# Passive_Balancing.net
KiCad netlist of a schematic drawn in Altium Designer
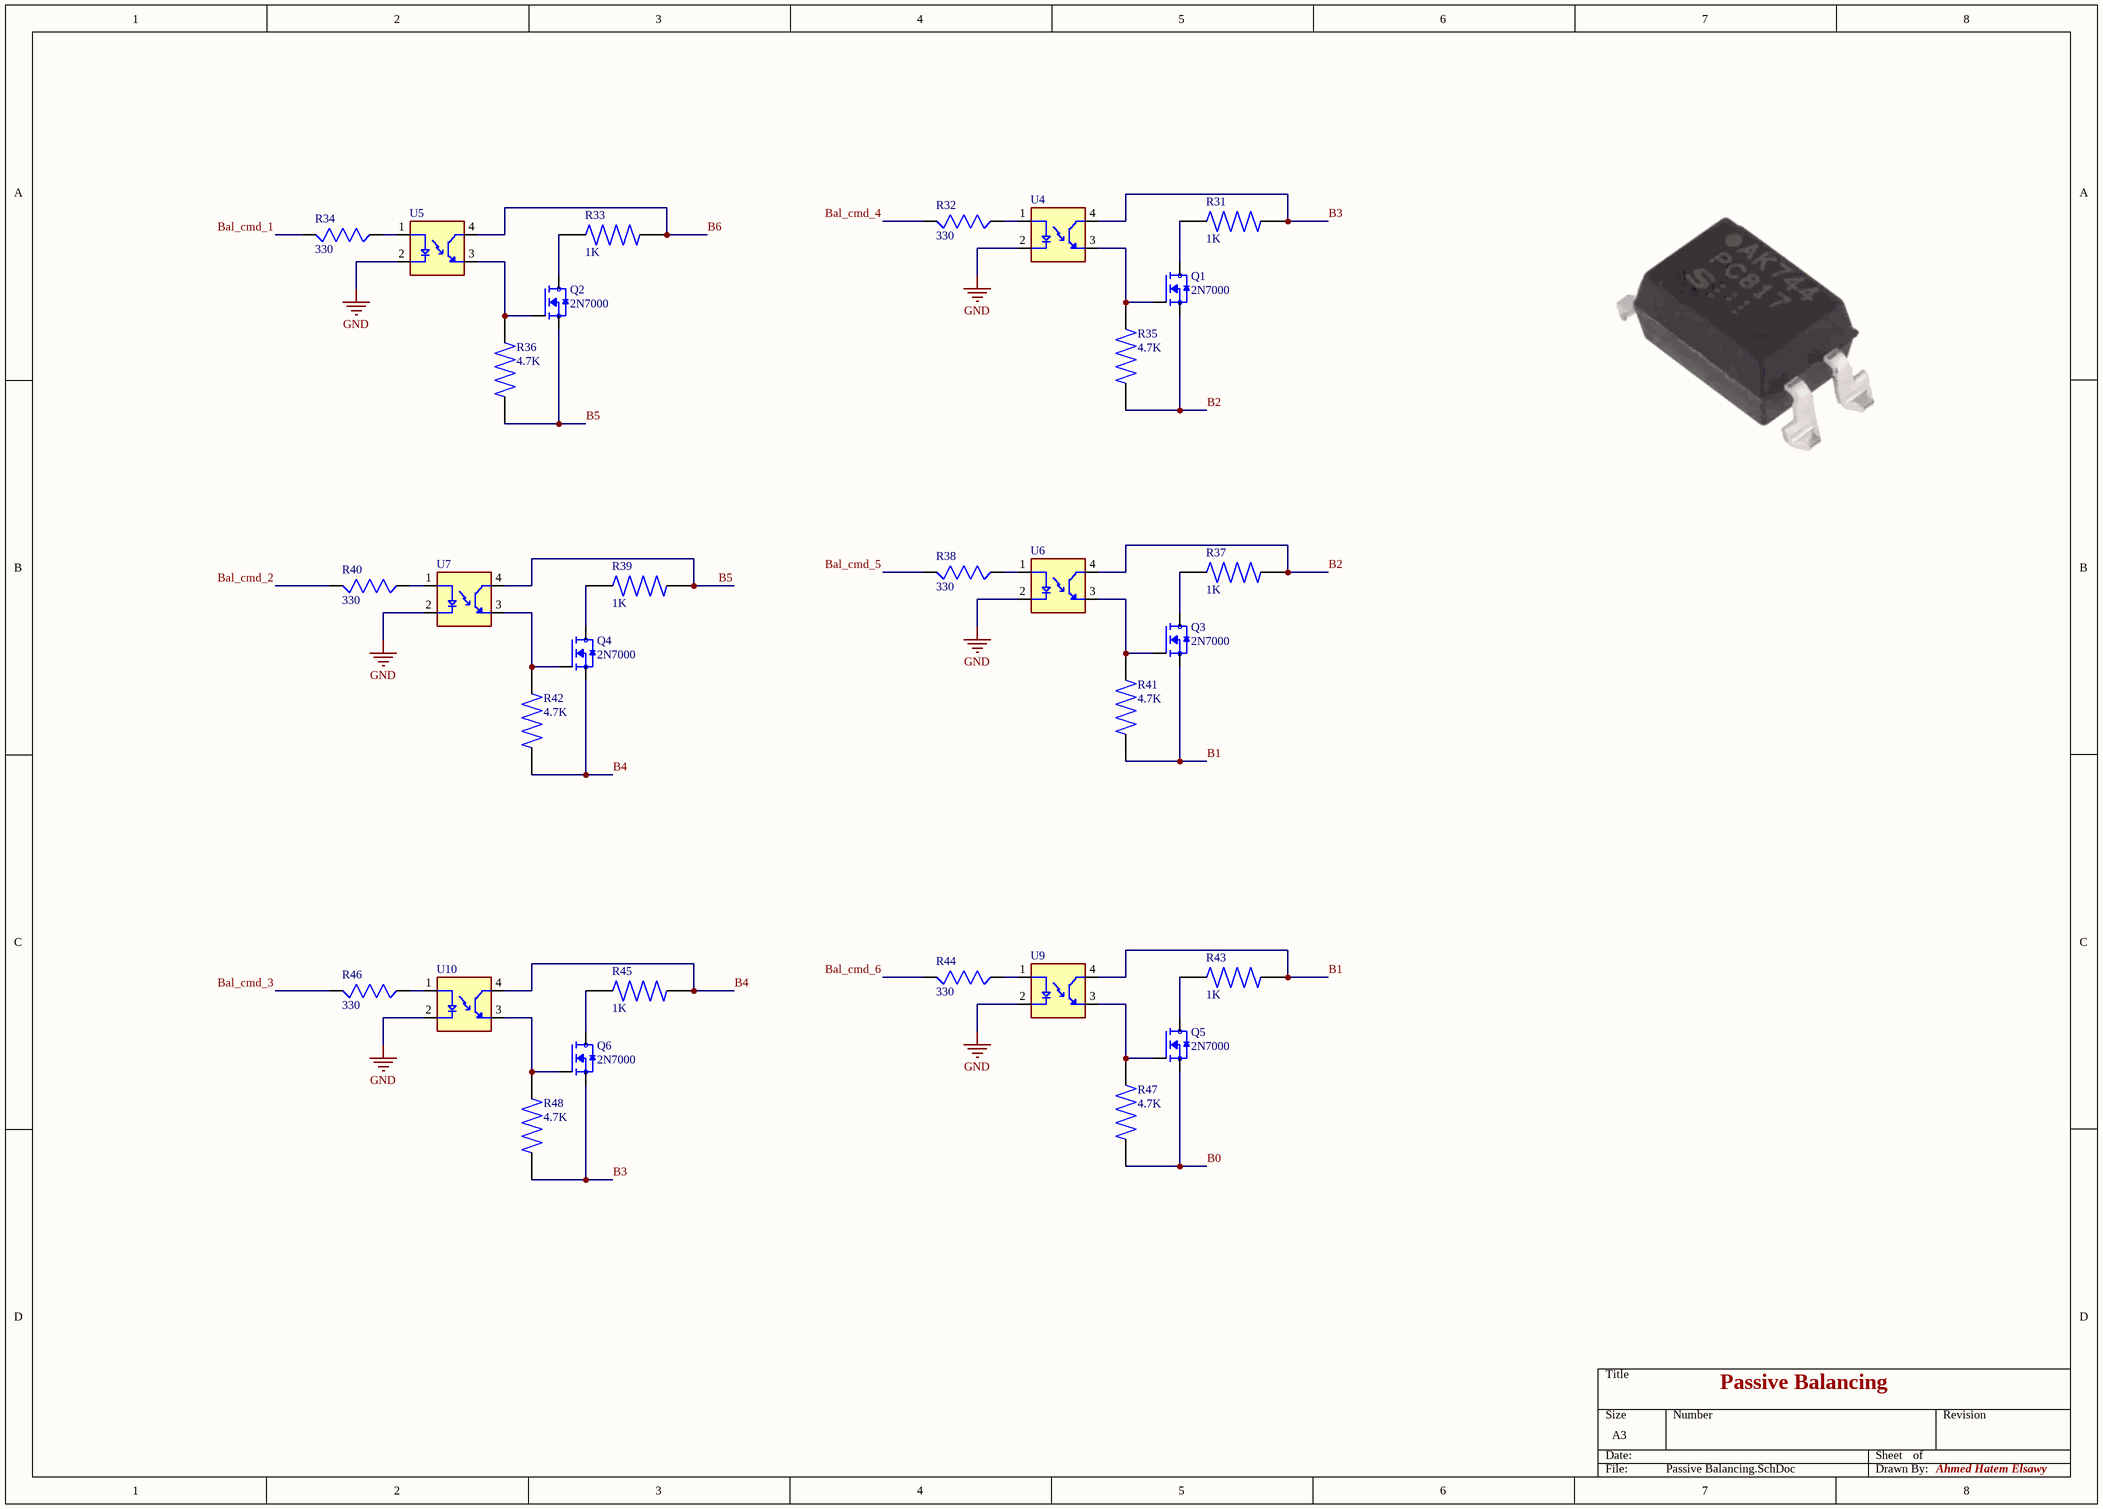
[diagram p0: Passive Balancing.SchDoc]

(export (version "E")
  (design (tool "Eeschema 10.0.6"))
  (components
    (comp (ref "Q1")
      (value "2N7000")
      (footprint "TO92254P458H750-3")
      (description "N-Channel 60 V 350mA (Tc) 1W (Tc) Through Hole TO-92-3")
      (fields (field (name "MF") "STMicroelectronics"))
      (libsource (lib "2N7000") (part "2N7000"))
    )
    (comp (ref "Q2")
      (value "2N7000")
      (footprint "TO92254P458H750-3")
      (description "N-Channel 60 V 350mA (Tc) 1W (Tc) Through Hole TO-92-3")
      (fields (field (name "MF") "STMicroelectronics"))
      (libsource (lib "2N7000") (part "2N7000"))
    )
    (comp (ref "Q3")
      (value "2N7000")
      (footprint "TO92254P458H750-3")
      (description "N-Channel 60 V 350mA (Tc) 1W (Tc) Through Hole TO-92-3")
      (fields (field (name "MF") "STMicroelectronics"))
      (libsource (lib "2N7000") (part "2N7000"))
    )
    (comp (ref "Q4")
      (value "2N7000")
      (footprint "TO92254P458H750-3")
      (description "N-Channel 60 V 350mA (Tc) 1W (Tc) Through Hole TO-92-3")
      (fields (field (name "MF") "STMicroelectronics"))
      (libsource (lib "2N7000") (part "2N7000"))
    )
    (comp (ref "Q5")
      (value "2N7000")
      (footprint "TO92254P458H750-3")
      (description "N-Channel 60 V 350mA (Tc) 1W (Tc) Through Hole TO-92-3")
      (fields (field (name "MF") "STMicroelectronics"))
      (libsource (lib "2N7000") (part "2N7000"))
    )
    (comp (ref "Q6")
      (value "2N7000")
      (footprint "TO92254P458H750-3")
      (description "N-Channel 60 V 350mA (Tc) 1W (Tc) Through Hole TO-92-3")
      (fields (field (name "MF") "STMicroelectronics"))
      (libsource (lib "2N7000") (part "2N7000"))
    )
    (comp (ref "R31")
      (value "1K")
      (footprint "RESC1608X55N")
      (description "DirenÃ§, AS 0603 1k %1 100mW TC100 ¦ Bourns CR0603AFX-1001EAS")
      (fields (field (name "MF") "Bourns") (field (name "MP") "CR0603AFX-1001EAS"))
      (libsource (lib "CR0603AFX-1001EAS") (part "CR0603AFX-1001EAS"))
    )
    (comp (ref "R32")
      (value "330")
      (footprint "RESC3216X65")
      (description "Res Thick Film 1206 330 Ohm 5% 0.25W(1/4W) Â±100ppm/Â°C Epoxy Pad SMD T/R")
      (fields (field (name "MF") "Yageo Corporation") (field (name "MP") "RC1206JR13330RL"))
      (libsource (lib "RC1206JR-13330RL") (part "RC1206JR-13330RL"))
    )
    (comp (ref "R33")
      (value "1K")
      (footprint "RESC1608X55N")
      (description "DirenÃ§, AS 0603 1k %1 100mW TC100 ¦ Bourns CR0603AFX-1001EAS")
      (fields (field (name "MF") "Bourns") (field (name "MP") "CR0603AFX-1001EAS"))
      (libsource (lib "CR0603AFX-1001EAS") (part "CR0603AFX-1001EAS"))
    )
    (comp (ref "R34")
      (value "330")
      (footprint "RESC3216X65")
      (description "Res Thick Film 1206 330 Ohm 5% 0.25W(1/4W) Â±100ppm/Â°C Epoxy Pad SMD T/R")
      (fields (field (name "MF") "Yageo Corporation") (field (name "MP") "RC1206JR13330RL"))
      (libsource (lib "RC1206JR-13330RL") (part "RC1206JR-13330RL"))
    )
    (comp (ref "R35")
      (value "4.7K")
      (footprint "RES_ERJS06J472V")
      (fields (field (name "MP") "ERJS06J472V"))
      (libsource (lib "ERJS06J472V") (part "ERJS06J472V"))
    )
    (comp (ref "R36")
      (value "4.7K")
      (footprint "RES_ERJS06J472V")
      (fields (field (name "MP") "ERJS06J472V"))
      (libsource (lib "ERJS06J472V") (part "ERJS06J472V"))
    )
    (comp (ref "R37")
      (value "1K")
      (footprint "RESC1608X55N")
      (description "DirenÃ§, AS 0603 1k %1 100mW TC100 ¦ Bourns CR0603AFX-1001EAS")
      (fields (field (name "MF") "Bourns") (field (name "MP") "CR0603AFX-1001EAS"))
      (libsource (lib "CR0603AFX-1001EAS") (part "CR0603AFX-1001EAS"))
    )
    (comp (ref "R38")
      (value "330")
      (footprint "RESC3216X65")
      (description "Res Thick Film 1206 330 Ohm 5% 0.25W(1/4W) Â±100ppm/Â°C Epoxy Pad SMD T/R")
      (fields (field (name "MF") "Yageo Corporation") (field (name "MP") "RC1206JR13330RL"))
      (libsource (lib "RC1206JR-13330RL") (part "RC1206JR-13330RL"))
    )
    (comp (ref "R39")
      (value "1K")
      (footprint "RESC1608X55N")
      (description "DirenÃ§, AS 0603 1k %1 100mW TC100 ¦ Bourns CR0603AFX-1001EAS")
      (fields (field (name "MF") "Bourns") (field (name "MP") "CR0603AFX-1001EAS"))
      (libsource (lib "CR0603AFX-1001EAS") (part "CR0603AFX-1001EAS"))
    )
    (comp (ref "R40")
      (value "330")
      (footprint "RESC3216X65")
      (description "Res Thick Film 1206 330 Ohm 5% 0.25W(1/4W) Â±100ppm/Â°C Epoxy Pad SMD T/R")
      (fields (field (name "MF") "Yageo Corporation") (field (name "MP") "RC1206JR13330RL"))
      (libsource (lib "RC1206JR-13330RL") (part "RC1206JR-13330RL"))
    )
    (comp (ref "R41")
      (value "4.7K")
      (footprint "RES_ERJS06J472V")
      (fields (field (name "MP") "ERJS06J472V"))
      (libsource (lib "ERJS06J472V") (part "ERJS06J472V"))
    )
    (comp (ref "R42")
      (value "4.7K")
      (footprint "RES_ERJS06J472V")
      (fields (field (name "MP") "ERJS06J472V"))
      (libsource (lib "ERJS06J472V") (part "ERJS06J472V"))
    )
    (comp (ref "R43")
      (value "1K")
      (footprint "RESC1608X55N")
      (description "DirenÃ§, AS 0603 1k %1 100mW TC100 ¦ Bourns CR0603AFX-1001EAS")
      (fields (field (name "MF") "Bourns") (field (name "MP") "CR0603AFX-1001EAS"))
      (libsource (lib "CR0603AFX-1001EAS") (part "CR0603AFX-1001EAS"))
    )
    (comp (ref "R44")
      (value "330")
      (footprint "RESC3216X65")
      (description "Res Thick Film 1206 330 Ohm 5% 0.25W(1/4W) Â±100ppm/Â°C Epoxy Pad SMD T/R")
      (fields (field (name "MF") "Yageo Corporation") (field (name "MP") "RC1206JR13330RL"))
      (libsource (lib "RC1206JR-13330RL") (part "RC1206JR-13330RL"))
    )
    (comp (ref "R45")
      (value "1K")
      (footprint "RESC1608X55N")
      (description "DirenÃ§, AS 0603 1k %1 100mW TC100 ¦ Bourns CR0603AFX-1001EAS")
      (fields (field (name "MF") "Bourns") (field (name "MP") "CR0603AFX-1001EAS"))
      (libsource (lib "CR0603AFX-1001EAS") (part "CR0603AFX-1001EAS"))
    )
    (comp (ref "R46")
      (value "330")
      (footprint "RESC3216X65")
      (description "Res Thick Film 1206 330 Ohm 5% 0.25W(1/4W) Â±100ppm/Â°C Epoxy Pad SMD T/R")
      (fields (field (name "MF") "Yageo Corporation") (field (name "MP") "RC1206JR13330RL"))
      (libsource (lib "RC1206JR-13330RL") (part "RC1206JR-13330RL"))
    )
    (comp (ref "R47")
      (value "4.7K")
      (footprint "RES_ERJS06J472V")
      (fields (field (name "MP") "ERJS06J472V"))
      (libsource (lib "ERJS06J472V") (part "ERJS06J472V"))
    )
    (comp (ref "R48")
      (value "4.7K")
      (footprint "RES_ERJS06J472V")
      (fields (field (name "MP") "ERJS06J472V"))
      (libsource (lib "ERJS06J472V") (part "ERJS06J472V"))
    )
    (comp (ref "U4")
      (value "PC817X2NIP1B")
      (footprint "SOIC254P960X420-4N")
      (description "Optocoupler DC-IN 1-CH Transistor DC-OUT 4-Pin DIP SMD T/R")
      (fields (field (name "MF") "Sharp Microelectronics"))
      (libsource (lib "PC817X2NIP1B") (part "PC817X2NIP1B"))
    )
    (comp (ref "U5")
      (value "PC817X2NIP1B")
      (footprint "SOIC254P960X420-4N")
      (description "Optocoupler DC-IN 1-CH Transistor DC-OUT 4-Pin DIP SMD T/R")
      (fields (field (name "MF") "Sharp Microelectronics"))
      (libsource (lib "PC817X2NIP1B") (part "PC817X2NIP1B"))
    )
    (comp (ref "U6")
      (value "PC817X2NIP1B")
      (footprint "SOIC254P960X420-4N")
      (description "Optocoupler DC-IN 1-CH Transistor DC-OUT 4-Pin DIP SMD T/R")
      (fields (field (name "MF") "Sharp Microelectronics"))
      (libsource (lib "PC817X2NIP1B") (part "PC817X2NIP1B"))
    )
    (comp (ref "U7")
      (value "PC817X2NIP1B")
      (footprint "SOIC254P960X420-4N")
      (description "Optocoupler DC-IN 1-CH Transistor DC-OUT 4-Pin DIP SMD T/R")
      (fields (field (name "MF") "Sharp Microelectronics"))
      (libsource (lib "PC817X2NIP1B") (part "PC817X2NIP1B"))
    )
    (comp (ref "U9")
      (value "PC817X2NIP1B")
      (footprint "SOIC254P960X420-4N")
      (description "Optocoupler DC-IN 1-CH Transistor DC-OUT 4-Pin DIP SMD T/R")
      (fields (field (name "MF") "Sharp Microelectronics"))
      (libsource (lib "PC817X2NIP1B") (part "PC817X2NIP1B"))
    )
    (comp (ref "U10")
      (value "PC817X2NIP1B")
      (footprint "SOIC254P960X420-4N")
      (description "Optocoupler DC-IN 1-CH Transistor DC-OUT 4-Pin DIP SMD T/R")
      (fields (field (name "MF") "Sharp Microelectronics"))
      (libsource (lib "PC817X2NIP1B") (part "PC817X2NIP1B"))
    )
  )
  (nets
    (net (code "2") (name "/B0") (class "Default")
      (node (ref "Q5") (pin "1") (pinfunction "S_1") (pintype "passive"))
      (node (ref "R47") (pin "1") (pinfunction "1_1") (pintype "passive"))
    )
    (net (code "3") (name "/B1") (class "Default")
      (node (ref "Q3") (pin "1") (pinfunction "S_1") (pintype "passive"))
      (node (ref "R41") (pin "1") (pinfunction "1_1") (pintype "passive"))
      (node (ref "R43") (pin "2") (pinfunction "2_2") (pintype "passive"))
      (node (ref "U9") (pin "4") (pinfunction "CT_4") (pintype "passive"))
    )
    (net (code "4") (name "/B2") (class "Default")
      (node (ref "Q1") (pin "1") (pinfunction "S_1") (pintype "passive"))
      (node (ref "R35") (pin "1") (pinfunction "1_1") (pintype "passive"))
      (node (ref "R37") (pin "2") (pinfunction "2_2") (pintype "passive"))
      (node (ref "U6") (pin "4") (pinfunction "CT_4") (pintype "passive"))
    )
    (net (code "5") (name "/B3") (class "Default")
      (node (ref "Q6") (pin "1") (pinfunction "S_1") (pintype "passive"))
      (node (ref "R31") (pin "2") (pinfunction "2_2") (pintype "passive"))
      (node (ref "R48") (pin "1") (pinfunction "1_1") (pintype "passive"))
      (node (ref "U4") (pin "4") (pinfunction "CT_4") (pintype "passive"))
    )
    (net (code "6") (name "/B4") (class "Default")
      (node (ref "Q4") (pin "1") (pinfunction "S_1") (pintype "passive"))
      (node (ref "R42") (pin "1") (pinfunction "1_1") (pintype "passive"))
      (node (ref "R45") (pin "2") (pinfunction "2_2") (pintype "passive"))
      (node (ref "U10") (pin "4") (pinfunction "CT_4") (pintype "passive"))
    )
    (net (code "7") (name "/B5") (class "Default")
      (node (ref "Q2") (pin "1") (pinfunction "S_1") (pintype "passive"))
      (node (ref "R36") (pin "1") (pinfunction "1_1") (pintype "passive"))
      (node (ref "R39") (pin "2") (pinfunction "2_2") (pintype "passive"))
      (node (ref "U7") (pin "4") (pinfunction "CT_4") (pintype "passive"))
    )
    (net (code "8") (name "/B6") (class "Default")
      (node (ref "R33") (pin "2") (pinfunction "2_2") (pintype "passive"))
      (node (ref "U5") (pin "4") (pinfunction "CT_4") (pintype "passive"))
    )
    (net (code "9") (name "/Bal_cmd_1") (class "Default")
      (node (ref "R34") (pin "1") (pinfunction "1_1") (pintype "passive"))
    )
    (net (code "10") (name "/Bal_cmd_2") (class "Default")
      (node (ref "R40") (pin "1") (pinfunction "1_1") (pintype "passive"))
    )
    (net (code "11") (name "/Bal_cmd_3") (class "Default")
      (node (ref "R46") (pin "1") (pinfunction "1_1") (pintype "passive"))
    )
    (net (code "12") (name "/Bal_cmd_4") (class "Default")
      (node (ref "R32") (pin "1") (pinfunction "1_1") (pintype "passive"))
    )
    (net (code "13") (name "/Bal_cmd_5") (class "Default")
      (node (ref "R38") (pin "1") (pinfunction "1_1") (pintype "passive"))
    )
    (net (code "14") (name "/Bal_cmd_6") (class "Default")
      (node (ref "R44") (pin "1") (pinfunction "1_1") (pintype "passive"))
    )
    (net (code "15") (name "GND") (class "Default")
      (node (ref "U10") (pin "2") (pinfunction "C_2") (pintype "passive"))
      (node (ref "U4") (pin "2") (pinfunction "C_2") (pintype "passive"))
      (node (ref "U5") (pin "2") (pinfunction "C_2") (pintype "passive"))
      (node (ref "U6") (pin "2") (pinfunction "C_2") (pintype "passive"))
      (node (ref "U7") (pin "2") (pinfunction "C_2") (pintype "passive"))
      (node (ref "U9") (pin "2") (pinfunction "C_2") (pintype "passive"))
    )
    (net (code "16") (name "Net-(Q1-D)") (class "Default")
      (node (ref "Q1") (pin "3") (pinfunction "D_3") (pintype "passive"))
      (node (ref "R31") (pin "1") (pinfunction "1_1") (pintype "passive"))
    )
    (net (code "17") (name "Net-(Q1-G)") (class "Default")
      (node (ref "Q1") (pin "2") (pinfunction "G_2") (pintype "passive"))
      (node (ref "R35") (pin "2") (pinfunction "2_2") (pintype "passive"))
      (node (ref "U4") (pin "3") (pinfunction "ET_3") (pintype "passive"))
    )
    (net (code "18") (name "Net-(Q2-D)") (class "Default")
      (node (ref "Q2") (pin "3") (pinfunction "D_3") (pintype "passive"))
      (node (ref "R33") (pin "1") (pinfunction "1_1") (pintype "passive"))
    )
    (net (code "19") (name "Net-(Q2-G)") (class "Default")
      (node (ref "Q2") (pin "2") (pinfunction "G_2") (pintype "passive"))
      (node (ref "R36") (pin "2") (pinfunction "2_2") (pintype "passive"))
      (node (ref "U5") (pin "3") (pinfunction "ET_3") (pintype "passive"))
    )
    (net (code "20") (name "Net-(Q3-D)") (class "Default")
      (node (ref "Q3") (pin "3") (pinfunction "D_3") (pintype "passive"))
      (node (ref "R37") (pin "1") (pinfunction "1_1") (pintype "passive"))
    )
    (net (code "21") (name "Net-(Q3-G)") (class "Default")
      (node (ref "Q3") (pin "2") (pinfunction "G_2") (pintype "passive"))
      (node (ref "R41") (pin "2") (pinfunction "2_2") (pintype "passive"))
      (node (ref "U6") (pin "3") (pinfunction "ET_3") (pintype "passive"))
    )
    (net (code "22") (name "Net-(Q4-D)") (class "Default")
      (node (ref "Q4") (pin "3") (pinfunction "D_3") (pintype "passive"))
      (node (ref "R39") (pin "1") (pinfunction "1_1") (pintype "passive"))
    )
    (net (code "23") (name "Net-(Q4-G)") (class "Default")
      (node (ref "Q4") (pin "2") (pinfunction "G_2") (pintype "passive"))
      (node (ref "R42") (pin "2") (pinfunction "2_2") (pintype "passive"))
      (node (ref "U7") (pin "3") (pinfunction "ET_3") (pintype "passive"))
    )
    (net (code "24") (name "Net-(Q5-D)") (class "Default")
      (node (ref "Q5") (pin "3") (pinfunction "D_3") (pintype "passive"))
      (node (ref "R43") (pin "1") (pinfunction "1_1") (pintype "passive"))
    )
    (net (code "25") (name "Net-(Q5-G)") (class "Default")
      (node (ref "Q5") (pin "2") (pinfunction "G_2") (pintype "passive"))
      (node (ref "R47") (pin "2") (pinfunction "2_2") (pintype "passive"))
      (node (ref "U9") (pin "3") (pinfunction "ET_3") (pintype "passive"))
    )
    (net (code "26") (name "Net-(Q6-D)") (class "Default")
      (node (ref "Q6") (pin "3") (pinfunction "D_3") (pintype "passive"))
      (node (ref "R45") (pin "1") (pinfunction "1_1") (pintype "passive"))
    )
    (net (code "27") (name "Net-(Q6-G)") (class "Default")
      (node (ref "Q6") (pin "2") (pinfunction "G_2") (pintype "passive"))
      (node (ref "R48") (pin "2") (pinfunction "2_2") (pintype "passive"))
      (node (ref "U10") (pin "3") (pinfunction "ET_3") (pintype "passive"))
    )
    (net (code "28") (name "Net-(U4-A)") (class "Default")
      (node (ref "R32") (pin "2") (pinfunction "2_2") (pintype "passive"))
      (node (ref "U4") (pin "1") (pinfunction "A_1") (pintype "passive"))
    )
    (net (code "29") (name "Net-(U5-A)") (class "Default")
      (node (ref "R34") (pin "2") (pinfunction "2_2") (pintype "passive"))
      (node (ref "U5") (pin "1") (pinfunction "A_1") (pintype "passive"))
    )
    (net (code "30") (name "Net-(U6-A)") (class "Default")
      (node (ref "R38") (pin "2") (pinfunction "2_2") (pintype "passive"))
      (node (ref "U6") (pin "1") (pinfunction "A_1") (pintype "passive"))
    )
    (net (code "31") (name "Net-(U7-A)") (class "Default")
      (node (ref "R40") (pin "2") (pinfunction "2_2") (pintype "passive"))
      (node (ref "U7") (pin "1") (pinfunction "A_1") (pintype "passive"))
    )
    (net (code "32") (name "Net-(U9-A)") (class "Default")
      (node (ref "R44") (pin "2") (pinfunction "2_2") (pintype "passive"))
      (node (ref "U9") (pin "1") (pinfunction "A_1") (pintype "passive"))
    )
    (net (code "33") (name "Net-(U10-A)") (class "Default")
      (node (ref "R46") (pin "2") (pinfunction "2_2") (pintype "passive"))
      (node (ref "U10") (pin "1") (pinfunction "A_1") (pintype "passive"))
    )
  )
)
